# MotherBoard_ver2.net
KiCad netlist of a schematic drawn in EAGLE
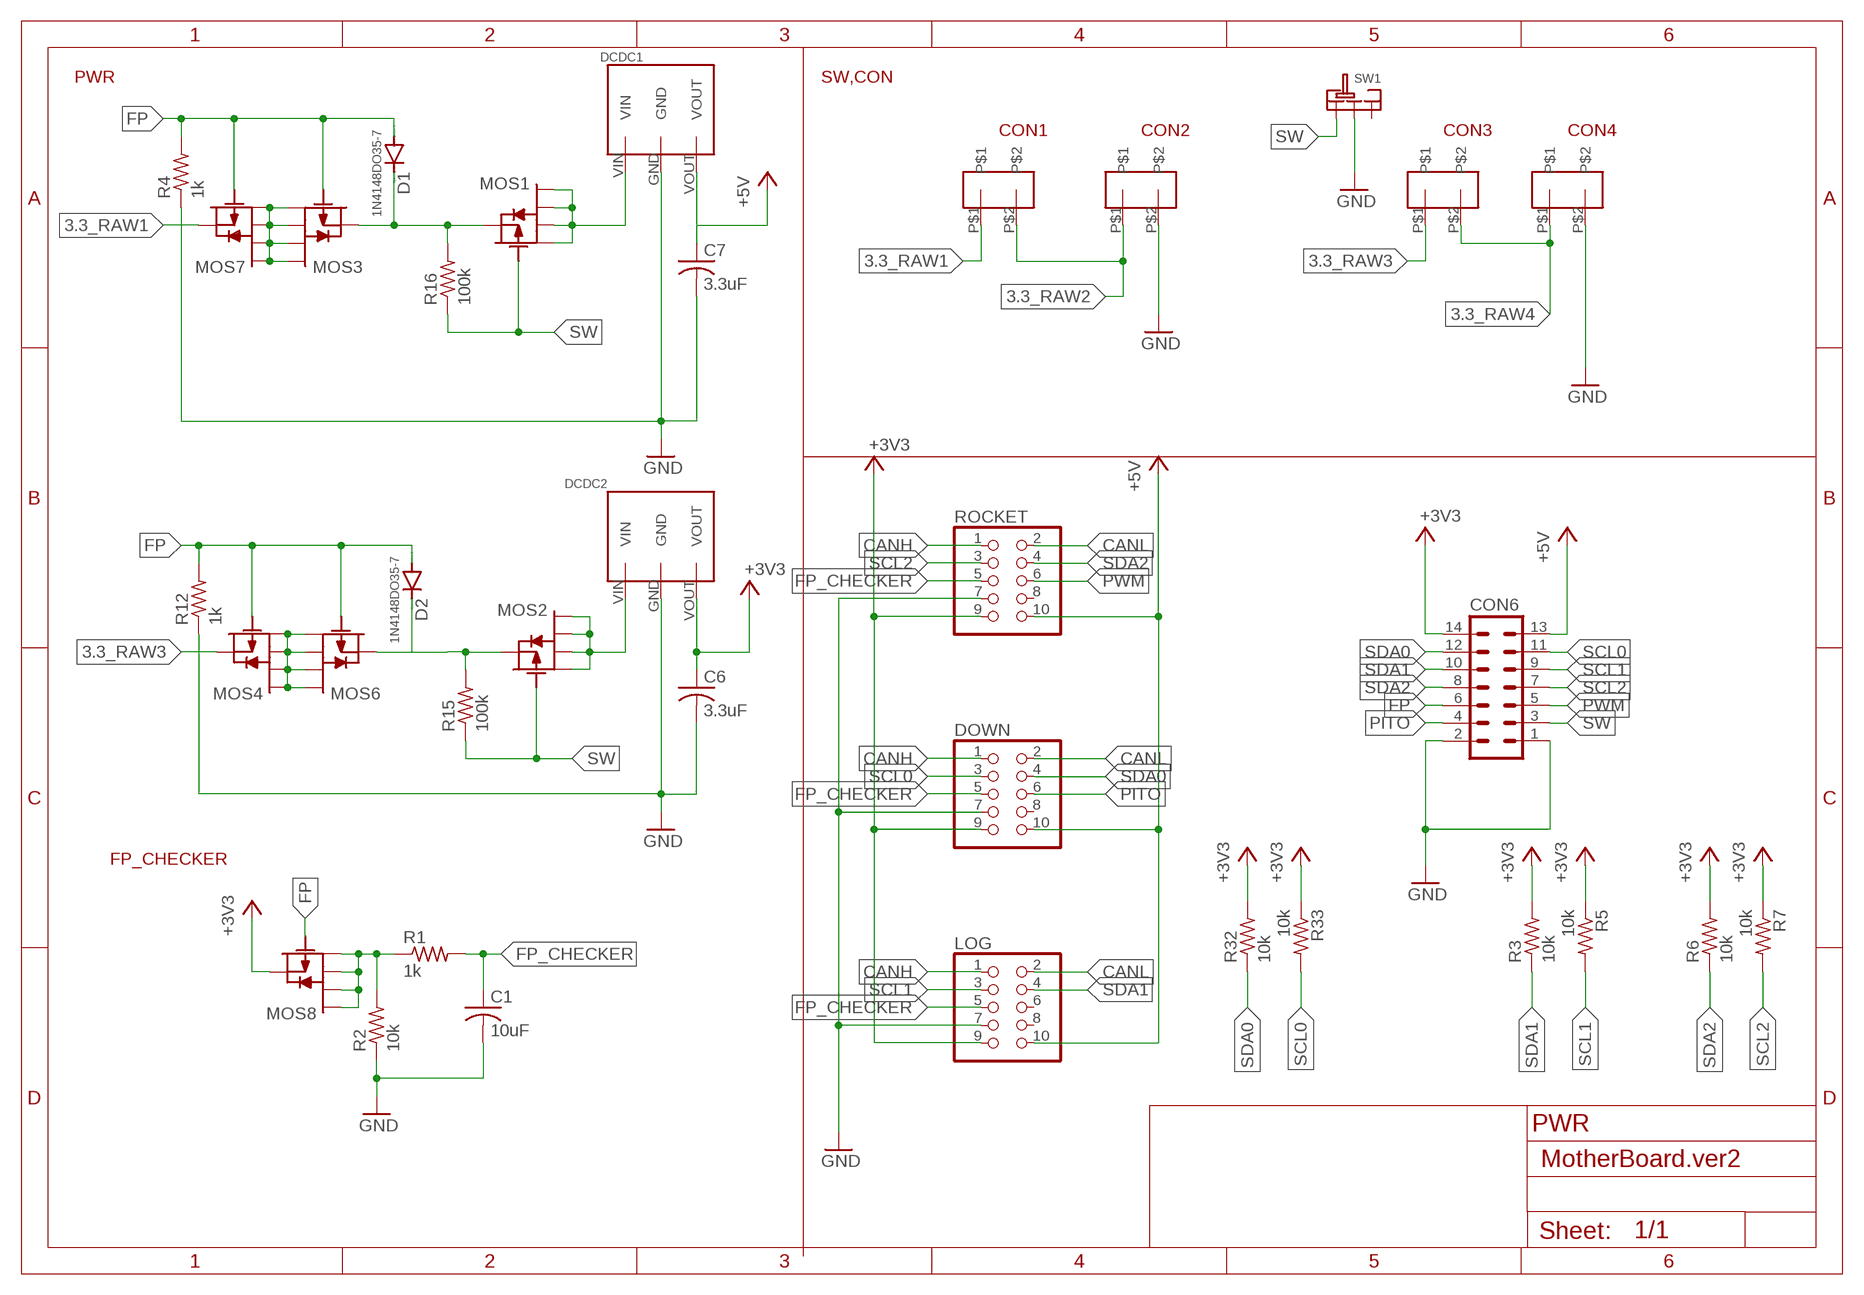
[diagram p0: schematic, sheet 1]

(export (version "E")
  (design (tool "Eeschema 10.0.6"))
  (components
    (comp (ref "C1")
      (value "10uF")
      (footprint "eagle-import:C0603")
      (libsource (lib "eagle-import") (part "C-USC0603"))
    )
    (comp (ref "C6")
      (value "3.3uF")
      (footprint "eagle-import:C0603")
      (libsource (lib "eagle-import") (part "C-USC0603"))
    )
    (comp (ref "C7")
      (value "3.3uF")
      (footprint "eagle-import:C0603")
      (libsource (lib "eagle-import") (part "C-USC0603"))
    )
    (comp (ref "CON1")
      (value "1.25CON2PIN")
      (footprint "eagle-import:1.25CON2PIN")
      (libsource (lib "eagle-import") (part "1.25CON2PIN"))
    )
    (comp (ref "CON2")
      (value "1.25CON2PIN")
      (footprint "eagle-import:1.25CON2PIN")
      (libsource (lib "eagle-import") (part "1.25CON2PIN"))
    )
    (comp (ref "CON3")
      (value "1.25CON2PIN")
      (footprint "eagle-import:1.25CON2PIN")
      (libsource (lib "eagle-import") (part "1.25CON2PIN"))
    )
    (comp (ref "CON4")
      (value "1.25CON2PIN")
      (footprint "eagle-import:1.25CON2PIN")
      (libsource (lib "eagle-import") (part "1.25CON2PIN"))
    )
    (comp (ref "CON6")
      (value "ML14L")
      (footprint "eagle-import:ML14L")
      (libsource (lib "eagle-import") (part "ML14L"))
    )
    (comp (ref "D1")
      (value "1N4148DO35-7")
      (footprint "eagle-import:DO35-7")
      (libsource (lib "eagle-import") (part "1N4148DO35-7"))
    )
    (comp (ref "D2")
      (value "1N4148DO35-7")
      (footprint "eagle-import:DO35-7")
      (libsource (lib "eagle-import") (part "1N4148DO35-7"))
    )
    (comp (ref "DCDC1")
      (value "5V1A_M78AR05-1")
      (footprint "eagle-import:5V1A_M78AR05-1")
      (libsource (lib "eagle-import") (part "5V1A_M78AR05-1"))
    )
    (comp (ref "DCDC2")
      (value "3.3V1A_M78AR033-1")
      (footprint "eagle-import:3.3V1A_M78AR033-1")
      (libsource (lib "eagle-import") (part "3.3V1A_M78AR033-1"))
    )
    (comp (ref "DOWN")
      (value "PINHD-2X5")
      (footprint "eagle-import:2X05")
      (libsource (lib "eagle-import") (part "PINHD-2X5"))
    )
    (comp (ref "LOG")
      (value "PINHD-2X5")
      (footprint "eagle-import:2X05")
      (libsource (lib "eagle-import") (part "PINHD-2X5"))
    )
    (comp (ref "MOS1")
      (value "PCH_SSM6J808R")
      (footprint "eagle-import:SSM6J808R")
      (libsource (lib "eagle-import") (part "PCH_SSM6J808R"))
    )
    (comp (ref "MOS2")
      (value "PCH_SSM6J808R")
      (footprint "eagle-import:SSM6J808R")
      (libsource (lib "eagle-import") (part "PCH_SSM6J808R"))
    )
    (comp (ref "MOS3")
      (value "PCH_SSM6J808R")
      (footprint "eagle-import:SSM6J808R")
      (libsource (lib "eagle-import") (part "PCH_SSM6J808R"))
    )
    (comp (ref "MOS4")
      (value "PCH_SSM6J808R")
      (footprint "eagle-import:SSM6J808R")
      (libsource (lib "eagle-import") (part "PCH_SSM6J808R"))
    )
    (comp (ref "MOS6")
      (value "PCH_SSM6J808R")
      (footprint "eagle-import:SSM6J808R")
      (libsource (lib "eagle-import") (part "PCH_SSM6J808R"))
    )
    (comp (ref "MOS7")
      (value "PCH_SSM6J808R")
      (footprint "eagle-import:SSM6J808R")
      (libsource (lib "eagle-import") (part "PCH_SSM6J808R"))
    )
    (comp (ref "MOS8")
      (value "PCH_SSM6J808R")
      (footprint "eagle-import:SSM6J808R")
      (libsource (lib "eagle-import") (part "PCH_SSM6J808R"))
    )
    (comp (ref "R1")
      (value "1k")
      (footprint "eagle-import:R0603")
      (libsource (lib "eagle-import") (part "R-US_R0603"))
    )
    (comp (ref "R2")
      (value "10k")
      (footprint "eagle-import:R0603")
      (libsource (lib "eagle-import") (part "R-US_R0603"))
    )
    (comp (ref "R3")
      (value "10k")
      (footprint "eagle-import:R0603")
      (libsource (lib "eagle-import") (part "R-US_R0603"))
    )
    (comp (ref "R4")
      (value "1k")
      (footprint "eagle-import:R0603")
      (libsource (lib "eagle-import") (part "R-US_R0603"))
    )
    (comp (ref "R5")
      (value "10k")
      (footprint "eagle-import:R0603")
      (libsource (lib "eagle-import") (part "R-US_R0603"))
    )
    (comp (ref "R6")
      (value "10k")
      (footprint "eagle-import:R0603")
      (libsource (lib "eagle-import") (part "R-US_R0603"))
    )
    (comp (ref "R7")
      (value "10k")
      (footprint "eagle-import:R0603")
      (libsource (lib "eagle-import") (part "R-US_R0603"))
    )
    (comp (ref "R12")
      (value "1k")
      (footprint "eagle-import:R0603")
      (libsource (lib "eagle-import") (part "R-US_R0603"))
    )
    (comp (ref "R15")
      (value "100k")
      (footprint "eagle-import:R0603")
      (libsource (lib "eagle-import") (part "R-US_R0603"))
    )
    (comp (ref "R16")
      (value "100k")
      (footprint "eagle-import:R0603")
      (libsource (lib "eagle-import") (part "R-US_R0603"))
    )
    (comp (ref "R32")
      (value "10k")
      (footprint "eagle-import:R0603")
      (libsource (lib "eagle-import") (part "R-US_R0603"))
    )
    (comp (ref "R33")
      (value "10k")
      (footprint "eagle-import:R0603")
      (libsource (lib "eagle-import") (part "R-US_R0603"))
    )
    (comp (ref "ROCKET")
      (value "PINHD-2X5")
      (footprint "eagle-import:2X05")
      (libsource (lib "eagle-import") (part "PINHD-2X5"))
    )
    (comp (ref "SW1")
      (value "SRIDE_SWITCH")
      (footprint "eagle-import:SRIDE_SWITCH")
      (libsource (lib "eagle-import") (part "SRIDE_SWITCH"))
    )
  )
  (nets
    (net (code "1") (name "+3V3") (class "Default")
      (node (ref "C6") (pin "1") (pinfunction "1_1") (pintype "passive"))
      (node (ref "CON6") (pin "14") (pinfunction "14_14") (pintype "passive"))
      (node (ref "DCDC2") (pin "VOUT") (pinfunction "VOUT_VOUT") (pintype "bidirectional"))
      (node (ref "DOWN") (pin "9") (pinfunction "9_9") (pintype "passive"))
      (node (ref "LOG") (pin "9") (pinfunction "9_9") (pintype "passive"))
      (node (ref "MOS8") (pin "4") (pinfunction "4_4") (pintype "bidirectional"))
      (node (ref "R3") (pin "2") (pinfunction "2_2") (pintype "passive"))
      (node (ref "R32") (pin "2") (pinfunction "2_2") (pintype "passive"))
      (node (ref "R33") (pin "1") (pinfunction "1_1") (pintype "passive"))
      (node (ref "R5") (pin "1") (pinfunction "1_1") (pintype "passive"))
      (node (ref "R6") (pin "2") (pinfunction "2_2") (pintype "passive"))
      (node (ref "R7") (pin "1") (pinfunction "1_1") (pintype "passive"))
      (node (ref "ROCKET") (pin "9") (pinfunction "9_9") (pintype "passive"))
    )
    (net (code "2") (name "+5V") (class "Default")
      (node (ref "C7") (pin "1") (pinfunction "1_1") (pintype "passive"))
      (node (ref "CON6") (pin "13") (pinfunction "13_13") (pintype "passive"))
      (node (ref "DCDC1") (pin "VOUT") (pinfunction "VOUT_VOUT") (pintype "bidirectional"))
      (node (ref "DOWN") (pin "10") (pinfunction "10_10") (pintype "passive"))
      (node (ref "LOG") (pin "10") (pinfunction "10_10") (pintype "passive"))
      (node (ref "ROCKET") (pin "10") (pinfunction "10_10") (pintype "passive"))
    )
    (net (code "3") (name "3.3_RAW1") (class "Default")
      (node (ref "CON1") (pin "P$1") (pinfunction "P$1_P$1") (pintype "bidirectional"))
      (node (ref "MOS7") (pin "4") (pinfunction "4_4") (pintype "bidirectional"))
    )
    (net (code "4") (name "3.3_RAW2") (class "Default")
      (node (ref "CON1") (pin "P$2") (pinfunction "P$2_P$2") (pintype "bidirectional"))
      (node (ref "CON2") (pin "P$1") (pinfunction "P$1_P$1") (pintype "bidirectional"))
    )
    (net (code "5") (name "3.3_RAW3") (class "Default")
      (node (ref "CON3") (pin "P$1") (pinfunction "P$1_P$1") (pintype "bidirectional"))
      (node (ref "MOS4") (pin "4") (pinfunction "4_4") (pintype "bidirectional"))
    )
    (net (code "6") (name "3.3_RAW4") (class "Default")
      (node (ref "CON3") (pin "P$2") (pinfunction "P$2_P$2") (pintype "bidirectional"))
      (node (ref "CON4") (pin "P$1") (pinfunction "P$1_P$1") (pintype "bidirectional"))
    )
    (net (code "7") (name "CANH") (class "Default")
      (node (ref "DOWN") (pin "1") (pinfunction "1_1") (pintype "passive"))
      (node (ref "LOG") (pin "1") (pinfunction "1_1") (pintype "passive"))
      (node (ref "ROCKET") (pin "1") (pinfunction "1_1") (pintype "passive"))
    )
    (net (code "8") (name "CANL") (class "Default")
      (node (ref "DOWN") (pin "2") (pinfunction "2_2") (pintype "passive"))
      (node (ref "LOG") (pin "2") (pinfunction "2_2") (pintype "passive"))
      (node (ref "ROCKET") (pin "2") (pinfunction "2_2") (pintype "passive"))
    )
    (net (code "9") (name "FP") (class "Default")
      (node (ref "CON6") (pin "6") (pinfunction "6_6") (pintype "passive"))
      (node (ref "D1") (pin "A") (pinfunction "A_A") (pintype "passive"))
      (node (ref "D2") (pin "A") (pinfunction "A_A") (pintype "passive"))
      (node (ref "MOS3") (pin "3") (pinfunction "3_3") (pintype "bidirectional"))
      (node (ref "MOS4") (pin "3") (pinfunction "3_3") (pintype "bidirectional"))
      (node (ref "MOS6") (pin "3") (pinfunction "3_3") (pintype "bidirectional"))
      (node (ref "MOS7") (pin "3") (pinfunction "3_3") (pintype "bidirectional"))
      (node (ref "MOS8") (pin "3") (pinfunction "3_3") (pintype "bidirectional"))
      (node (ref "R12") (pin "2") (pinfunction "2_2") (pintype "passive"))
      (node (ref "R4") (pin "2") (pinfunction "2_2") (pintype "passive"))
    )
    (net (code "10") (name "FP_CHECKER") (class "Default")
      (node (ref "C1") (pin "1") (pinfunction "1_1") (pintype "passive"))
      (node (ref "DOWN") (pin "5") (pinfunction "5_5") (pintype "passive"))
      (node (ref "LOG") (pin "5") (pinfunction "5_5") (pintype "passive"))
      (node (ref "R1") (pin "2") (pinfunction "2_2") (pintype "passive"))
      (node (ref "ROCKET") (pin "5") (pinfunction "5_5") (pintype "passive"))
    )
    (net (code "11") (name "GND") (class "Default")
      (node (ref "C1") (pin "2") (pinfunction "2_2") (pintype "passive"))
      (node (ref "C6") (pin "2") (pinfunction "2_2") (pintype "passive"))
      (node (ref "C7") (pin "2") (pinfunction "2_2") (pintype "passive"))
      (node (ref "CON2") (pin "P$2") (pinfunction "P$2_P$2") (pintype "bidirectional"))
      (node (ref "CON4") (pin "P$2") (pinfunction "P$2_P$2") (pintype "bidirectional"))
      (node (ref "CON6") (pin "1") (pinfunction "1_1") (pintype "passive"))
      (node (ref "CON6") (pin "2") (pinfunction "2_2") (pintype "passive"))
      (node (ref "DCDC1") (pin "GND") (pinfunction "GND_GND") (pintype "bidirectional"))
      (node (ref "DCDC2") (pin "GND") (pinfunction "GND_GND") (pintype "bidirectional"))
      (node (ref "DOWN") (pin "7") (pinfunction "7_7") (pintype "passive"))
      (node (ref "LOG") (pin "7") (pinfunction "7_7") (pintype "passive"))
      (node (ref "R12") (pin "1") (pinfunction "1_1") (pintype "passive"))
      (node (ref "R2") (pin "1") (pinfunction "1_1") (pintype "passive"))
      (node (ref "R4") (pin "1") (pinfunction "1_1") (pintype "passive"))
      (node (ref "ROCKET") (pin "7") (pinfunction "7_7") (pintype "passive"))
      (node (ref "SW1") (pin "LR") (pinfunction "LR_LR") (pintype "bidirectional"))
    )
    (net (code "12") (name "Net-(D1-PadC)") (class "Default")
      (node (ref "D1") (pin "C") (pinfunction "C_C") (pintype "passive"))
      (node (ref "MOS1") (pin "4") (pinfunction "4_4") (pintype "bidirectional"))
      (node (ref "MOS3") (pin "4") (pinfunction "4_4") (pintype "bidirectional"))
      (node (ref "R16") (pin "2") (pinfunction "2_2") (pintype "passive"))
    )
    (net (code "13") (name "Net-(D2-PadC)") (class "Default")
      (node (ref "D2") (pin "C") (pinfunction "C_C") (pintype "passive"))
      (node (ref "MOS2") (pin "4") (pinfunction "4_4") (pintype "bidirectional"))
      (node (ref "MOS6") (pin "4") (pinfunction "4_4") (pintype "bidirectional"))
      (node (ref "R15") (pin "2") (pinfunction "2_2") (pintype "passive"))
    )
    (net (code "14") (name "Net-(DCDC1-PadVIN)") (class "Default")
      (node (ref "DCDC1") (pin "VIN") (pinfunction "VIN_VIN") (pintype "bidirectional"))
      (node (ref "MOS1") (pin "1") (pinfunction "1_1") (pintype "bidirectional"))
      (node (ref "MOS1") (pin "2") (pinfunction "2_2") (pintype "bidirectional"))
      (node (ref "MOS1") (pin "5") (pinfunction "5_5") (pintype "bidirectional"))
      (node (ref "MOS1") (pin "6") (pinfunction "6_6") (pintype "bidirectional"))
    )
    (net (code "15") (name "Net-(DCDC2-PadVIN)") (class "Default")
      (node (ref "DCDC2") (pin "VIN") (pinfunction "VIN_VIN") (pintype "bidirectional"))
      (node (ref "MOS2") (pin "1") (pinfunction "1_1") (pintype "bidirectional"))
      (node (ref "MOS2") (pin "2") (pinfunction "2_2") (pintype "bidirectional"))
      (node (ref "MOS2") (pin "5") (pinfunction "5_5") (pintype "bidirectional"))
      (node (ref "MOS2") (pin "6") (pinfunction "6_6") (pintype "bidirectional"))
    )
    (net (code "16") (name "Net-(MOS3-Pad1)") (class "Default")
      (node (ref "MOS3") (pin "1") (pinfunction "1_1") (pintype "bidirectional"))
      (node (ref "MOS3") (pin "2") (pinfunction "2_2") (pintype "bidirectional"))
      (node (ref "MOS3") (pin "5") (pinfunction "5_5") (pintype "bidirectional"))
      (node (ref "MOS3") (pin "6") (pinfunction "6_6") (pintype "bidirectional"))
      (node (ref "MOS7") (pin "1") (pinfunction "1_1") (pintype "bidirectional"))
      (node (ref "MOS7") (pin "2") (pinfunction "2_2") (pintype "bidirectional"))
      (node (ref "MOS7") (pin "5") (pinfunction "5_5") (pintype "bidirectional"))
      (node (ref "MOS7") (pin "6") (pinfunction "6_6") (pintype "bidirectional"))
    )
    (net (code "17") (name "Net-(MOS4-Pad1)") (class "Default")
      (node (ref "MOS4") (pin "1") (pinfunction "1_1") (pintype "bidirectional"))
      (node (ref "MOS4") (pin "2") (pinfunction "2_2") (pintype "bidirectional"))
      (node (ref "MOS4") (pin "5") (pinfunction "5_5") (pintype "bidirectional"))
      (node (ref "MOS4") (pin "6") (pinfunction "6_6") (pintype "bidirectional"))
      (node (ref "MOS6") (pin "1") (pinfunction "1_1") (pintype "bidirectional"))
      (node (ref "MOS6") (pin "2") (pinfunction "2_2") (pintype "bidirectional"))
      (node (ref "MOS6") (pin "5") (pinfunction "5_5") (pintype "bidirectional"))
      (node (ref "MOS6") (pin "6") (pinfunction "6_6") (pintype "bidirectional"))
    )
    (net (code "18") (name "Net-(MOS8-Pad1)") (class "Default")
      (node (ref "MOS8") (pin "1") (pinfunction "1_1") (pintype "bidirectional"))
      (node (ref "MOS8") (pin "2") (pinfunction "2_2") (pintype "bidirectional"))
      (node (ref "MOS8") (pin "5") (pinfunction "5_5") (pintype "bidirectional"))
      (node (ref "MOS8") (pin "6") (pinfunction "6_6") (pintype "bidirectional"))
      (node (ref "R1") (pin "1") (pinfunction "1_1") (pintype "passive"))
      (node (ref "R2") (pin "2") (pinfunction "2_2") (pintype "passive"))
    )
    (net (code "19") (name "PITO") (class "Default")
      (node (ref "CON6") (pin "4") (pinfunction "4_4") (pintype "passive"))
      (node (ref "DOWN") (pin "6") (pinfunction "6_6") (pintype "passive"))
    )
    (net (code "20") (name "PWM") (class "Default")
      (node (ref "CON6") (pin "5") (pinfunction "5_5") (pintype "passive"))
      (node (ref "ROCKET") (pin "6") (pinfunction "6_6") (pintype "passive"))
    )
    (net (code "21") (name "SCL0") (class "Default")
      (node (ref "CON6") (pin "11") (pinfunction "11_11") (pintype "passive"))
      (node (ref "DOWN") (pin "3") (pinfunction "3_3") (pintype "passive"))
      (node (ref "R33") (pin "2") (pinfunction "2_2") (pintype "passive"))
    )
    (net (code "22") (name "SCL1") (class "Default")
      (node (ref "CON6") (pin "9") (pinfunction "9_9") (pintype "passive"))
      (node (ref "LOG") (pin "3") (pinfunction "3_3") (pintype "passive"))
      (node (ref "R5") (pin "2") (pinfunction "2_2") (pintype "passive"))
    )
    (net (code "23") (name "SCL2") (class "Default")
      (node (ref "CON6") (pin "7") (pinfunction "7_7") (pintype "passive"))
      (node (ref "R7") (pin "2") (pinfunction "2_2") (pintype "passive"))
      (node (ref "ROCKET") (pin "3") (pinfunction "3_3") (pintype "passive"))
    )
    (net (code "24") (name "SDA0") (class "Default")
      (node (ref "CON6") (pin "12") (pinfunction "12_12") (pintype "passive"))
      (node (ref "DOWN") (pin "4") (pinfunction "4_4") (pintype "passive"))
      (node (ref "R32") (pin "1") (pinfunction "1_1") (pintype "passive"))
    )
    (net (code "25") (name "SDA1") (class "Default")
      (node (ref "CON6") (pin "10") (pinfunction "10_10") (pintype "passive"))
      (node (ref "LOG") (pin "4") (pinfunction "4_4") (pintype "passive"))
      (node (ref "R3") (pin "1") (pinfunction "1_1") (pintype "passive"))
    )
    (net (code "26") (name "SDA2") (class "Default")
      (node (ref "CON6") (pin "8") (pinfunction "8_8") (pintype "passive"))
      (node (ref "R6") (pin "1") (pinfunction "1_1") (pintype "passive"))
      (node (ref "ROCKET") (pin "4") (pinfunction "4_4") (pintype "passive"))
    )
    (net (code "27") (name "SW") (class "Default")
      (node (ref "CON6") (pin "3") (pinfunction "3_3") (pintype "passive"))
      (node (ref "MOS1") (pin "3") (pinfunction "3_3") (pintype "bidirectional"))
      (node (ref "MOS2") (pin "3") (pinfunction "3_3") (pintype "bidirectional"))
      (node (ref "R15") (pin "1") (pinfunction "1_1") (pintype "passive"))
      (node (ref "R16") (pin "1") (pinfunction "1_1") (pintype "passive"))
      (node (ref "SW1") (pin "L") (pinfunction "L_L") (pintype "bidirectional"))
    )
    (net (code "28") (name "unconnected-(DOWN-Pad8)") (class "Default")
      (node (ref "DOWN") (pin "8") (pinfunction "8_8") (pintype "passive"))
    )
    (net (code "29") (name "unconnected-(LOG-Pad6)") (class "Default")
      (node (ref "LOG") (pin "6") (pinfunction "6_6") (pintype "passive"))
    )
    (net (code "30") (name "unconnected-(LOG-Pad8)") (class "Default")
      (node (ref "LOG") (pin "8") (pinfunction "8_8") (pintype "passive"))
    )
    (net (code "31") (name "unconnected-(ROCKET-Pad8)") (class "Default")
      (node (ref "ROCKET") (pin "8") (pinfunction "8_8") (pintype "passive"))
    )
    (net (code "32") (name "unconnected-(SW1-PadR)") (class "Default")
      (node (ref "SW1") (pin "R") (pinfunction "R_R") (pintype "bidirectional"))
    )
  )
)
